# wristband.net
KiCad netlist of a schematic drawn in EAGLE
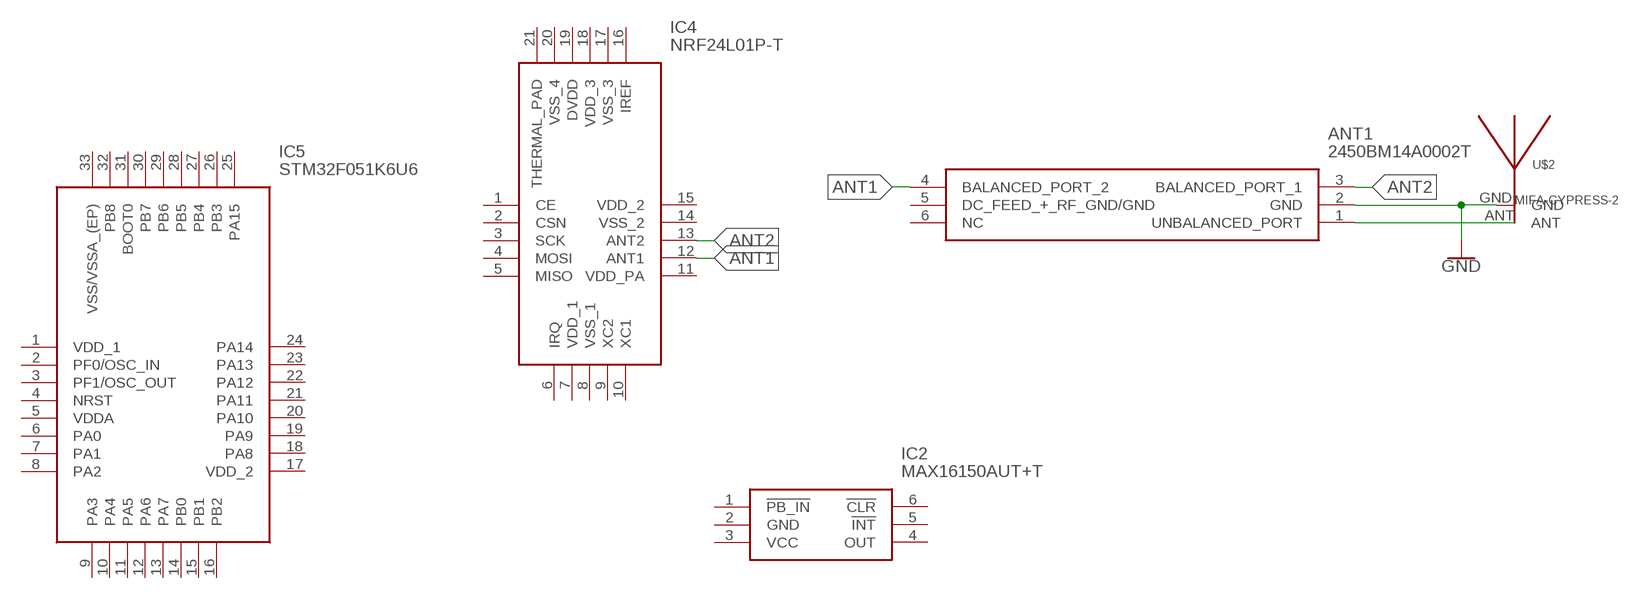
[diagram p0: schematic, sheet 1]

(export (version "E")
  (design (tool "Eeschema 10.0.6"))
  (components
    (comp (ref "ANT1")
      (value "2450BM14A0002T")
      (footprint "eagle-import:2450BM14A0002T")
      (fields (field (name "MOUSER_PART_NUMBER") "609-2450BM14A0002T"))
      (libsource (lib "eagle-import") (part "2450BM14A0002T"))
    )
    (comp (ref "IC2")
      (value "MAX16150AUT+T")
      (footprint "eagle-import:SOT95P280X145-6N")
      (fields (field (name "MOUSER_PART_NUMBER") "700-MAX16150AUT+T"))
      (libsource (lib "eagle-import") (part "MAX16150AUT+T"))
    )
    (comp (ref "IC4")
      (value "NRF24L01P-T")
      (footprint "eagle-import:QFN50P400X400X95-21N")
      (fields
        (field (name "MANUFACTURER_PART_NUMBER") "nRF24L01P-T")
        (field (name "MOUSER_PART_NUMBER") "949-NRF24L01P-T")
      )
      (libsource (lib "eagle-import") (part "NRF24L01P-T"))
    )
    (comp (ref "IC5")
      (value "STM32F051K6U6")
      (footprint "eagle-import:QFN50P500X500X60-33N")
      (fields (field (name "MOUSER_PART_NUMBER") "511-STM32F051K6U6"))
      (libsource (lib "eagle-import") (part "STM32F051K6U6"))
    )
    (comp (ref "U$2")
      (value "MIFA-CYPRESS-2")
      (footprint "eagle-import:MIFA-CYPRESS-2")
      (libsource (lib "eagle-import") (part "MIFA-CYPRESS-2"))
    )
  )
  (nets
    (net (code "1") (name "/VDDA") (class "Default")
      (node (ref "IC5") (pin "5") (pinfunction "VDDA_5") (pintype "power_in"))
    )
    (net (code "2") (name "/VDD_1") (class "Default")
      (node (ref "IC5") (pin "1") (pinfunction "VDD_1_1") (pintype "power_in"))
    )
    (net (code "3") (name "/VDD_2") (class "Default")
      (node (ref "IC5") (pin "17") (pinfunction "VDD_2_17") (pintype "power_in"))
    )
    (net (code "4") (name "/VSS{slash}VSSA_(EP)") (class "Default")
      (node (ref "IC5") (pin "33") (pinfunction "VSS/VSSA_(EP)_33") (pintype "power_in"))
    )
    (net (code "5") (name "ANT1") (class "Default")
      (node (ref "ANT1") (pin "4") (pinfunction "BALANCED_PORT_2_4") (pintype "bidirectional"))
      (node (ref "IC4") (pin "12") (pinfunction "ANT1_12") (pintype "bidirectional"))
    )
    (net (code "6") (name "ANT2") (class "Default")
      (node (ref "ANT1") (pin "3") (pinfunction "BALANCED_PORT_1_3") (pintype "bidirectional"))
      (node (ref "IC4") (pin "13") (pinfunction "ANT2_13") (pintype "bidirectional"))
    )
    (net (code "7") (name "GND") (class "Default")
      (node (ref "ANT1") (pin "2") (pinfunction "GND_2") (pintype "bidirectional"))
      (node (ref "U$2") (pin "GND") (pinfunction "GND_GND") (pintype "bidirectional"))
    )
    (net (code "8") (name "Net-(ANT1-UNBALANCED_PORT)") (class "Default")
      (node (ref "ANT1") (pin "1") (pinfunction "UNBALANCED_PORT_1") (pintype "bidirectional"))
      (node (ref "U$2") (pin "ANT") (pinfunction "ANT_ANT") (pintype "bidirectional"))
    )
    (net (code "9") (name "unconnected-(ANT1-DC_FEED_+_RF_GND{slash}GND-Pad5)") (class "Default")
      (node (ref "ANT1") (pin "5") (pinfunction "DC_FEED_+_RF_GND/GND_5") (pintype "bidirectional"))
    )
    (net (code "10") (name "unconnected-(ANT1-NC-Pad6)") (class "Default")
      (node (ref "ANT1") (pin "6") (pinfunction "NC_6") (pintype "no_connect"))
    )
    (net (code "11") (name "unconnected-(IC2-GND-Pad2)") (class "Default")
      (node (ref "IC2") (pin "2") (pinfunction "GND_2") (pintype "bidirectional"))
    )
    (net (code "12") (name "unconnected-(IC2-OUT-Pad4)") (class "Default")
      (node (ref "IC2") (pin "4") (pinfunction "OUT_4") (pintype "bidirectional"))
    )
    (net (code "13") (name "unconnected-(IC2-VCC-Pad3)") (class "Default")
      (node (ref "IC2") (pin "3") (pinfunction "VCC_3") (pintype "bidirectional"))
    )
    (net (code "14") (name "unconnected-(IC2-~{CLR}-Pad6)") (class "Default")
      (node (ref "IC2") (pin "6") (pinfunction "~{CLR}_6") (pintype "bidirectional"))
    )
    (net (code "15") (name "unconnected-(IC2-~{INT}-Pad5)") (class "Default")
      (node (ref "IC2") (pin "5") (pinfunction "~{INT}_5") (pintype "bidirectional"))
    )
    (net (code "16") (name "unconnected-(IC2-~{PB_IN}-Pad1)") (class "Default")
      (node (ref "IC2") (pin "1") (pinfunction "~{PB_IN}_1") (pintype "bidirectional"))
    )
    (net (code "17") (name "unconnected-(IC4-CE-Pad1)") (class "Default")
      (node (ref "IC4") (pin "1") (pinfunction "CE_1") (pintype "bidirectional"))
    )
    (net (code "18") (name "unconnected-(IC4-CSN-Pad2)") (class "Default")
      (node (ref "IC4") (pin "2") (pinfunction "CSN_2") (pintype "bidirectional"))
    )
    (net (code "19") (name "unconnected-(IC4-DVDD-Pad19)") (class "Default")
      (node (ref "IC4") (pin "19") (pinfunction "DVDD_19") (pintype "bidirectional"))
    )
    (net (code "20") (name "unconnected-(IC4-IREF-Pad16)") (class "Default")
      (node (ref "IC4") (pin "16") (pinfunction "IREF_16") (pintype "bidirectional"))
    )
    (net (code "21") (name "unconnected-(IC4-IRQ-Pad6)") (class "Default")
      (node (ref "IC4") (pin "6") (pinfunction "IRQ_6") (pintype "bidirectional"))
    )
    (net (code "22") (name "unconnected-(IC4-MISO-Pad5)") (class "Default")
      (node (ref "IC4") (pin "5") (pinfunction "MISO_5") (pintype "bidirectional"))
    )
    (net (code "23") (name "unconnected-(IC4-MOSI-Pad4)") (class "Default")
      (node (ref "IC4") (pin "4") (pinfunction "MOSI_4") (pintype "bidirectional"))
    )
    (net (code "24") (name "unconnected-(IC4-SCK-Pad3)") (class "Default")
      (node (ref "IC4") (pin "3") (pinfunction "SCK_3") (pintype "bidirectional"))
    )
    (net (code "25") (name "unconnected-(IC4-THERMAL_PAD-Pad21)") (class "Default")
      (node (ref "IC4") (pin "21") (pinfunction "THERMAL_PAD_21") (pintype "bidirectional"))
    )
    (net (code "26") (name "unconnected-(IC4-VDD_1-Pad7)") (class "Default")
      (node (ref "IC4") (pin "7") (pinfunction "VDD_1_7") (pintype "bidirectional"))
    )
    (net (code "27") (name "unconnected-(IC4-VDD_2-Pad15)") (class "Default")
      (node (ref "IC4") (pin "15") (pinfunction "VDD_2_15") (pintype "bidirectional"))
    )
    (net (code "28") (name "unconnected-(IC4-VDD_3-Pad18)") (class "Default")
      (node (ref "IC4") (pin "18") (pinfunction "VDD_3_18") (pintype "bidirectional"))
    )
    (net (code "29") (name "unconnected-(IC4-VDD_PA-Pad11)") (class "Default")
      (node (ref "IC4") (pin "11") (pinfunction "VDD_PA_11") (pintype "bidirectional"))
    )
    (net (code "30") (name "unconnected-(IC4-VSS_1-Pad8)") (class "Default")
      (node (ref "IC4") (pin "8") (pinfunction "VSS_1_8") (pintype "bidirectional"))
    )
    (net (code "31") (name "unconnected-(IC4-VSS_2-Pad14)") (class "Default")
      (node (ref "IC4") (pin "14") (pinfunction "VSS_2_14") (pintype "bidirectional"))
    )
    (net (code "32") (name "unconnected-(IC4-VSS_3-Pad17)") (class "Default")
      (node (ref "IC4") (pin "17") (pinfunction "VSS_3_17") (pintype "bidirectional"))
    )
    (net (code "33") (name "unconnected-(IC4-VSS_4-Pad20)") (class "Default")
      (node (ref "IC4") (pin "20") (pinfunction "VSS_4_20") (pintype "bidirectional"))
    )
    (net (code "34") (name "unconnected-(IC4-XC1-Pad10)") (class "Default")
      (node (ref "IC4") (pin "10") (pinfunction "XC1_10") (pintype "bidirectional"))
    )
    (net (code "35") (name "unconnected-(IC4-XC2-Pad9)") (class "Default")
      (node (ref "IC4") (pin "9") (pinfunction "XC2_9") (pintype "bidirectional"))
    )
    (net (code "36") (name "unconnected-(IC5-BOOT0-Pad31)") (class "Default")
      (node (ref "IC5") (pin "31") (pinfunction "BOOT0_31") (pintype "bidirectional"))
    )
    (net (code "37") (name "unconnected-(IC5-NRST-Pad4)") (class "Default")
      (node (ref "IC5") (pin "4") (pinfunction "NRST_4") (pintype "input"))
    )
    (net (code "38") (name "unconnected-(IC5-PA0-Pad6)") (class "Default")
      (node (ref "IC5") (pin "6") (pinfunction "PA0_6") (pintype "bidirectional"))
    )
    (net (code "39") (name "unconnected-(IC5-PA1-Pad7)") (class "Default")
      (node (ref "IC5") (pin "7") (pinfunction "PA1_7") (pintype "bidirectional"))
    )
    (net (code "40") (name "unconnected-(IC5-PA2-Pad8)") (class "Default")
      (node (ref "IC5") (pin "8") (pinfunction "PA2_8") (pintype "bidirectional"))
    )
    (net (code "41") (name "unconnected-(IC5-PA3-Pad9)") (class "Default")
      (node (ref "IC5") (pin "9") (pinfunction "PA3_9") (pintype "bidirectional"))
    )
    (net (code "42") (name "unconnected-(IC5-PA4-Pad10)") (class "Default")
      (node (ref "IC5") (pin "10") (pinfunction "PA4_10") (pintype "bidirectional"))
    )
    (net (code "43") (name "unconnected-(IC5-PA5-Pad11)") (class "Default")
      (node (ref "IC5") (pin "11") (pinfunction "PA5_11") (pintype "bidirectional"))
    )
    (net (code "44") (name "unconnected-(IC5-PA6-Pad12)") (class "Default")
      (node (ref "IC5") (pin "12") (pinfunction "PA6_12") (pintype "bidirectional"))
    )
    (net (code "45") (name "unconnected-(IC5-PA7-Pad13)") (class "Default")
      (node (ref "IC5") (pin "13") (pinfunction "PA7_13") (pintype "bidirectional"))
    )
    (net (code "46") (name "unconnected-(IC5-PA8-Pad18)") (class "Default")
      (node (ref "IC5") (pin "18") (pinfunction "PA8_18") (pintype "bidirectional"))
    )
    (net (code "47") (name "unconnected-(IC5-PA9-Pad19)") (class "Default")
      (node (ref "IC5") (pin "19") (pinfunction "PA9_19") (pintype "bidirectional"))
    )
    (net (code "48") (name "unconnected-(IC5-PA10-Pad20)") (class "Default")
      (node (ref "IC5") (pin "20") (pinfunction "PA10_20") (pintype "bidirectional"))
    )
    (net (code "49") (name "unconnected-(IC5-PA11-Pad21)") (class "Default")
      (node (ref "IC5") (pin "21") (pinfunction "PA11_21") (pintype "bidirectional"))
    )
    (net (code "50") (name "unconnected-(IC5-PA12-Pad22)") (class "Default")
      (node (ref "IC5") (pin "22") (pinfunction "PA12_22") (pintype "bidirectional"))
    )
    (net (code "51") (name "unconnected-(IC5-PA13-Pad23)") (class "Default")
      (node (ref "IC5") (pin "23") (pinfunction "PA13_23") (pintype "bidirectional"))
    )
    (net (code "52") (name "unconnected-(IC5-PA14-Pad24)") (class "Default")
      (node (ref "IC5") (pin "24") (pinfunction "PA14_24") (pintype "bidirectional"))
    )
    (net (code "53") (name "unconnected-(IC5-PA15-Pad25)") (class "Default")
      (node (ref "IC5") (pin "25") (pinfunction "PA15_25") (pintype "bidirectional"))
    )
    (net (code "54") (name "unconnected-(IC5-PB0-Pad14)") (class "Default")
      (node (ref "IC5") (pin "14") (pinfunction "PB0_14") (pintype "bidirectional"))
    )
    (net (code "55") (name "unconnected-(IC5-PB1-Pad15)") (class "Default")
      (node (ref "IC5") (pin "15") (pinfunction "PB1_15") (pintype "bidirectional"))
    )
    (net (code "56") (name "unconnected-(IC5-PB2-Pad16)") (class "Default")
      (node (ref "IC5") (pin "16") (pinfunction "PB2_16") (pintype "bidirectional"))
    )
    (net (code "57") (name "unconnected-(IC5-PB3-Pad26)") (class "Default")
      (node (ref "IC5") (pin "26") (pinfunction "PB3_26") (pintype "bidirectional"))
    )
    (net (code "58") (name "unconnected-(IC5-PB4-Pad27)") (class "Default")
      (node (ref "IC5") (pin "27") (pinfunction "PB4_27") (pintype "bidirectional"))
    )
    (net (code "59") (name "unconnected-(IC5-PB5-Pad28)") (class "Default")
      (node (ref "IC5") (pin "28") (pinfunction "PB5_28") (pintype "bidirectional"))
    )
    (net (code "60") (name "unconnected-(IC5-PB6-Pad29)") (class "Default")
      (node (ref "IC5") (pin "29") (pinfunction "PB6_29") (pintype "bidirectional"))
    )
    (net (code "61") (name "unconnected-(IC5-PB7-Pad30)") (class "Default")
      (node (ref "IC5") (pin "30") (pinfunction "PB7_30") (pintype "bidirectional"))
    )
    (net (code "62") (name "unconnected-(IC5-PB8-Pad32)") (class "Default")
      (node (ref "IC5") (pin "32") (pinfunction "PB8_32") (pintype "bidirectional"))
    )
    (net (code "63") (name "unconnected-(IC5-PF0{slash}OSC_IN-Pad2)") (class "Default")
      (node (ref "IC5") (pin "2") (pinfunction "PF0/OSC_IN_2") (pintype "input"))
    )
    (net (code "64") (name "unconnected-(IC5-PF1{slash}OSC_OUT-Pad3)") (class "Default")
      (node (ref "IC5") (pin "3") (pinfunction "PF1/OSC_OUT_3") (pintype "output"))
    )
  )
)
